# Surface_V2_0.net
KiCad netlist of a schematic drawn in Altium Designer
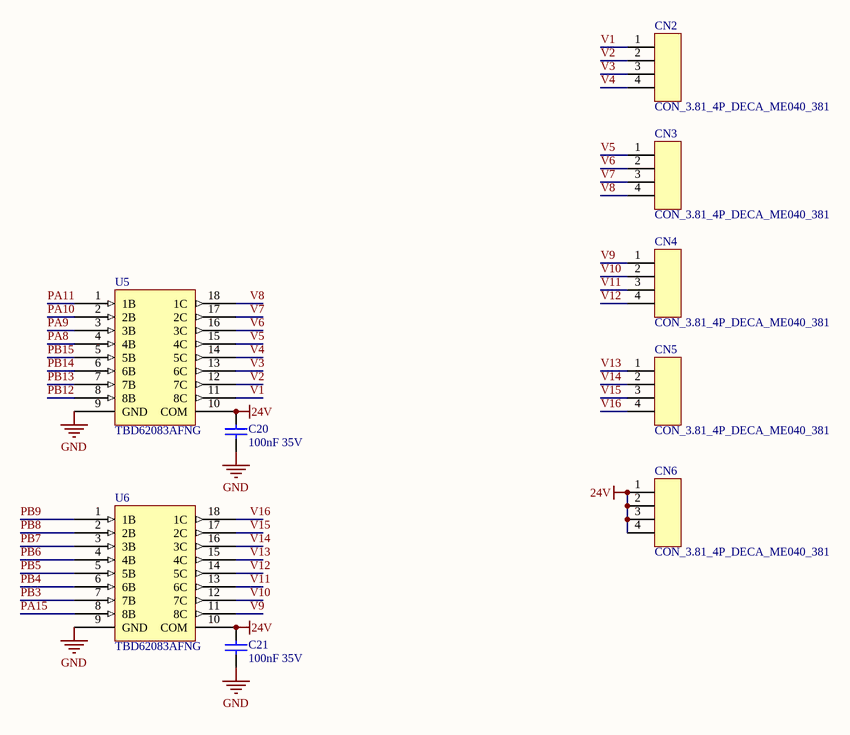
[diagram p0: Surface V2.0.SchDoc]

(export (version "E")
  (design (tool "Eeschema 10.0.6"))
  (components
    (comp (ref "C20") (value "100nF 35V") (footprint "C0603") (libsource (lib "stm32_s") (part "CAP")))
    (comp (ref "C21") (value "100nF 35V") (footprint "C0603") (libsource (lib "stm32_s") (part "CAP")))
    (comp (ref "CN2")
      (value "CON_3.81_4P_DECA_ME040_381")
      (footprint "ME040_381_4P_VC-1")
      (description "DECA connector,3.81mm,1*4P,180度")
      (fields (field (name "MANUFACTURER") "DECA") (field (name "PARTNUMBER") "ME040-381-4P"))
      (libsource (lib "Schlib1") (part "CON_3.81_4P_DECA_ME040_381"))
    )
    (comp (ref "CN3")
      (value "CON_3.81_4P_DECA_ME040_381")
      (footprint "ME040_381_4P_VC-1")
      (description "DECA connector,3.81mm,1*4P,180度")
      (fields (field (name "MANUFACTURER") "DECA") (field (name "PARTNUMBER") "ME040-381-4P"))
      (libsource (lib "Schlib1") (part "CON_3.81_4P_DECA_ME040_381"))
    )
    (comp (ref "CN4")
      (value "CON_3.81_4P_DECA_ME040_381")
      (footprint "ME040_381_4P_VC-1")
      (description "DECA connector,3.81mm,1*4P,180度")
      (fields (field (name "MANUFACTURER") "DECA") (field (name "PARTNUMBER") "ME040-381-4P"))
      (libsource (lib "Schlib1") (part "CON_3.81_4P_DECA_ME040_381"))
    )
    (comp (ref "CN5")
      (value "CON_3.81_4P_DECA_ME040_381")
      (footprint "ME040_381_4P_VC-1")
      (description "DECA connector,3.81mm,1*4P,180度")
      (fields (field (name "MANUFACTURER") "DECA") (field (name "PARTNUMBER") "ME040-381-4P"))
      (libsource (lib "Schlib1") (part "CON_3.81_4P_DECA_ME040_381"))
    )
    (comp (ref "CN6")
      (value "CON_3.81_4P_DECA_ME040_381")
      (footprint "ME040_381_4P_VC-1")
      (description "DECA connector,3.81mm,1*4P,180度")
      (fields (field (name "MANUFACTURER") "DECA") (field (name "PARTNUMBER") "ME040-381-4P"))
      (libsource (lib "Schlib1") (part "CON_3.81_4P_DECA_ME040_381"))
    )
    (comp (ref "U5")
      (value "TBD62083AFNG")
      (footprint "SSOP18-0.65")
      (description "达林顿晶体管阵列")
      (libsource (lib "库") (part "ULN2803"))
    )
    (comp (ref "U6")
      (value "TBD62083AFNG")
      (footprint "SSOP18-0.65")
      (description "达林顿晶体管阵列")
      (libsource (lib "库") (part "ULN2803"))
    )
  )
  (nets
    (net (code "1") (name "/PA8") (class "Default")
      (node (ref "U5") (pin "4") (pinfunction "4B_4") (pintype "input"))
    )
    (net (code "2") (name "/PA9") (class "Default")
      (node (ref "U5") (pin "3") (pinfunction "3B_3") (pintype "input"))
    )
    (net (code "3") (name "/PA10") (class "Default")
      (node (ref "U5") (pin "2") (pinfunction "2B_2") (pintype "input"))
    )
    (net (code "4") (name "/PA11") (class "Default")
      (node (ref "U5") (pin "1") (pinfunction "1B_1") (pintype "input"))
    )
    (net (code "5") (name "/PA15") (class "Default")
      (node (ref "U6") (pin "8") (pinfunction "8B_8") (pintype "input"))
    )
    (net (code "6") (name "/PB3") (class "Default")
      (node (ref "U6") (pin "7") (pinfunction "7B_7") (pintype "input"))
    )
    (net (code "7") (name "/PB4") (class "Default")
      (node (ref "U6") (pin "6") (pinfunction "6B_6") (pintype "input"))
    )
    (net (code "8") (name "/PB5") (class "Default")
      (node (ref "U6") (pin "5") (pinfunction "5B_5") (pintype "input"))
    )
    (net (code "9") (name "/PB6") (class "Default")
      (node (ref "U6") (pin "4") (pinfunction "4B_4") (pintype "input"))
    )
    (net (code "10") (name "/PB7") (class "Default")
      (node (ref "U6") (pin "3") (pinfunction "3B_3") (pintype "input"))
    )
    (net (code "11") (name "/PB8") (class "Default")
      (node (ref "U6") (pin "2") (pinfunction "2B_2") (pintype "input"))
    )
    (net (code "12") (name "/PB9") (class "Default")
      (node (ref "U6") (pin "1") (pinfunction "1B_1") (pintype "input"))
    )
    (net (code "13") (name "/PB12") (class "Default")
      (node (ref "U5") (pin "8") (pinfunction "8B_8") (pintype "input"))
    )
    (net (code "14") (name "/PB13") (class "Default")
      (node (ref "U5") (pin "7") (pinfunction "7B_7") (pintype "input"))
    )
    (net (code "15") (name "/PB14") (class "Default")
      (node (ref "U5") (pin "6") (pinfunction "6B_6") (pintype "input"))
    )
    (net (code "16") (name "/PB15") (class "Default")
      (node (ref "U5") (pin "5") (pinfunction "5B_5") (pintype "input"))
    )
    (net (code "17") (name "/V1") (class "Default")
      (node (ref "CN2") (pin "1") (pinfunction "1_1") (pintype "passive"))
      (node (ref "U5") (pin "11") (pinfunction "8C_11") (pintype "output"))
    )
    (net (code "18") (name "/V2") (class "Default")
      (node (ref "CN2") (pin "2") (pinfunction "2_2") (pintype "passive"))
      (node (ref "U5") (pin "12") (pinfunction "7C_12") (pintype "output"))
    )
    (net (code "19") (name "/V3") (class "Default")
      (node (ref "CN2") (pin "3") (pinfunction "3_3") (pintype "passive"))
      (node (ref "U5") (pin "13") (pinfunction "6C_13") (pintype "output"))
    )
    (net (code "20") (name "/V4") (class "Default")
      (node (ref "CN2") (pin "4") (pinfunction "4_4") (pintype "passive"))
      (node (ref "U5") (pin "14") (pinfunction "5C_14") (pintype "output"))
    )
    (net (code "21") (name "/V5") (class "Default")
      (node (ref "CN3") (pin "1") (pinfunction "1_1") (pintype "passive"))
      (node (ref "U5") (pin "15") (pinfunction "4C_15") (pintype "output"))
    )
    (net (code "22") (name "/V6") (class "Default")
      (node (ref "CN3") (pin "2") (pinfunction "2_2") (pintype "passive"))
      (node (ref "U5") (pin "16") (pinfunction "3C_16") (pintype "output"))
    )
    (net (code "23") (name "/V7") (class "Default")
      (node (ref "CN3") (pin "3") (pinfunction "3_3") (pintype "passive"))
      (node (ref "U5") (pin "17") (pinfunction "2C_17") (pintype "output"))
    )
    (net (code "24") (name "/V8") (class "Default")
      (node (ref "CN3") (pin "4") (pinfunction "4_4") (pintype "passive"))
      (node (ref "U5") (pin "18") (pinfunction "1C_18") (pintype "output"))
    )
    (net (code "25") (name "/V9") (class "Default")
      (node (ref "CN4") (pin "1") (pinfunction "1_1") (pintype "passive"))
      (node (ref "U6") (pin "11") (pinfunction "8C_11") (pintype "output"))
    )
    (net (code "26") (name "/V10") (class "Default")
      (node (ref "CN4") (pin "2") (pinfunction "2_2") (pintype "passive"))
      (node (ref "U6") (pin "12") (pinfunction "7C_12") (pintype "output"))
    )
    (net (code "27") (name "/V11") (class "Default")
      (node (ref "CN4") (pin "3") (pinfunction "3_3") (pintype "passive"))
      (node (ref "U6") (pin "13") (pinfunction "6C_13") (pintype "output"))
    )
    (net (code "28") (name "/V12") (class "Default")
      (node (ref "CN4") (pin "4") (pinfunction "4_4") (pintype "passive"))
      (node (ref "U6") (pin "14") (pinfunction "5C_14") (pintype "output"))
    )
    (net (code "29") (name "/V13") (class "Default")
      (node (ref "CN5") (pin "1") (pinfunction "1_1") (pintype "passive"))
      (node (ref "U6") (pin "15") (pinfunction "4C_15") (pintype "output"))
    )
    (net (code "30") (name "/V14") (class "Default")
      (node (ref "CN5") (pin "2") (pinfunction "2_2") (pintype "passive"))
      (node (ref "U6") (pin "16") (pinfunction "3C_16") (pintype "output"))
    )
    (net (code "31") (name "/V15") (class "Default")
      (node (ref "CN5") (pin "3") (pinfunction "3_3") (pintype "passive"))
      (node (ref "U6") (pin "17") (pinfunction "2C_17") (pintype "output"))
    )
    (net (code "32") (name "/V16") (class "Default")
      (node (ref "CN5") (pin "4") (pinfunction "4_4") (pintype "passive"))
      (node (ref "U6") (pin "18") (pinfunction "1C_18") (pintype "output"))
    )
    (net (code "33") (name "24V") (class "Default")
      (node (ref "C20") (pin "2") (pinfunction "2_2") (pintype "passive"))
      (node (ref "C21") (pin "2") (pinfunction "2_2") (pintype "passive"))
      (node (ref "CN6") (pin "1") (pinfunction "1_1") (pintype "passive"))
      (node (ref "CN6") (pin "2") (pinfunction "2_2") (pintype "passive"))
      (node (ref "CN6") (pin "3") (pinfunction "3_3") (pintype "passive"))
      (node (ref "CN6") (pin "4") (pinfunction "4_4") (pintype "passive"))
      (node (ref "U5") (pin "10") (pinfunction "COM_10") (pintype "power_in"))
      (node (ref "U6") (pin "10") (pinfunction "COM_10") (pintype "power_in"))
    )
    (net (code "34") (name "GND") (class "Default")
      (node (ref "C20") (pin "1") (pinfunction "1_1") (pintype "passive"))
      (node (ref "C21") (pin "1") (pinfunction "1_1") (pintype "passive"))
      (node (ref "U5") (pin "9") (pinfunction "GND_9") (pintype "power_in"))
      (node (ref "U6") (pin "9") (pinfunction "GND_9") (pintype "power_in"))
    )
  )
)
